# Wifi.net
KiCad netlist of a schematic drawn in Altium Designer
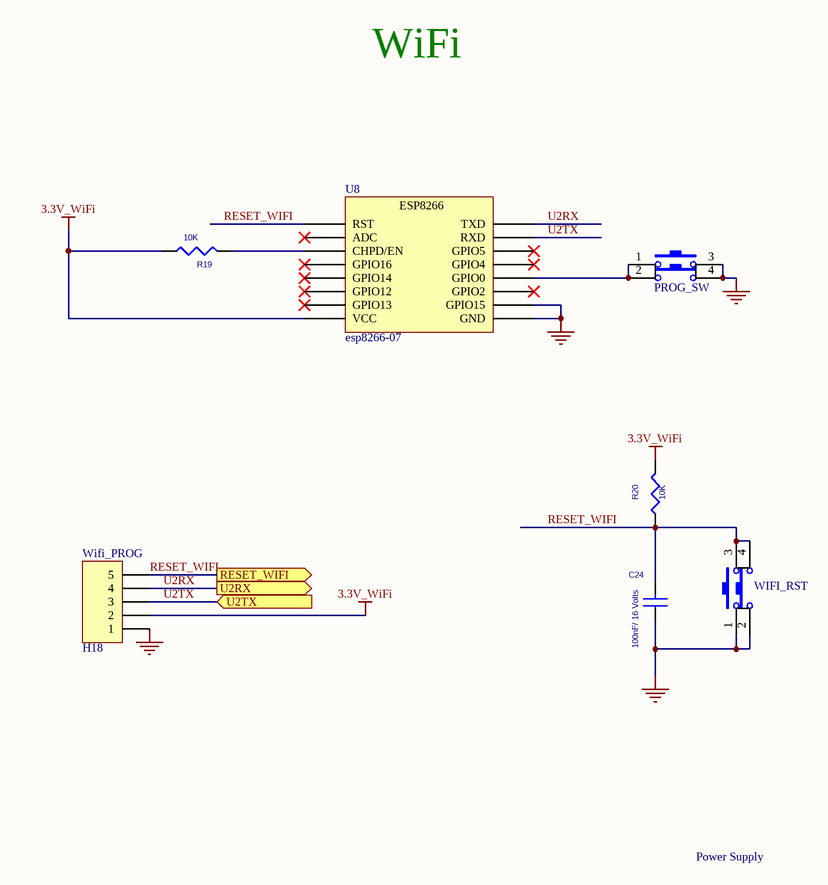
[diagram p0: Wifi.SchDoc]

(export (version "E")
  (design (tool "Eeschema 10.0.6"))
  (components
    (comp (ref "C24")
      (value "100nF/ 16 Volts")
      (footprint "CAP_CERAMIC")
      (libsource (lib "combined_cart_schematic_lib") (part "CAP NP"))
    )
    (comp (ref "PROG_SW")
      (value "SW-SMD")
      (footprint "SWITCH_SMD")
      (description "Switch")
      (fields (field (name "PUBLISHER") "Altium Limited"))
      (libsource (lib "combined_cart_schematic_lib") (part "SW-SMD"))
    )
    (comp (ref "R19")
      (value "10K")
      (footprint "RES_SMD")
      (libsource (lib "combined_cart_schematic_lib") (part "RESISTOR"))
    )
    (comp (ref "R20")
      (value "10K")
      (footprint "RES_SMD")
      (libsource (lib "combined_cart_schematic_lib") (part "RESISTOR"))
    )
    (comp (ref "U8")
      (value "esp8266-07")
      (footprint "esp8266-07")
      (fields (field (name "PUBLISHER") "Altium Limited"))
      (libsource (lib "combined_cart_schematic_lib") (part "esp8266-07"))
    )
    (comp (ref "Wifi_PROG")
      (value "H18")
      (footprint "1x5_single")
      (description "Header, 5-Pin")
      (fields (field (name "PUBLISHER") "Altium Limited"))
      (libsource (lib "combined_cart_schematic_lib") (part "Header 5"))
    )
    (comp (ref "WIFI_RST")
      (value "SW-SMD")
      (footprint "SWITCH_SMD")
      (description "Switch")
      (fields (field (name "PUBLISHER") "Altium Limited"))
      (libsource (lib "combined_cart_schematic_lib") (part "SW-SMD"))
    )
  )
  (nets
    (net (code "1") (name "/RESET_WIFI") (class "Default")
      (node (ref "C24") (pin "2") (pinfunction "2_2") (pintype "passive"))
      (node (ref "R20") (pin "1") (pinfunction "1_1") (pintype "passive"))
      (node (ref "U8") (pin "0") (pinfunction "RST_0") (pintype "passive"))
      (node (ref "WIFI_RST") (pin "3") (pintype "passive"))
      (node (ref "WIFI_RST") (pin "4") (pintype "passive"))
      (node (ref "Wifi_PROG") (pin "5") (pinfunction "5_5") (pintype "passive"))
    )
    (net (code "2") (name "/U2RX") (class "Default")
      (node (ref "U8") (pin "15") (pinfunction "TXD_15") (pintype "passive"))
      (node (ref "Wifi_PROG") (pin "4") (pinfunction "4_4") (pintype "passive"))
    )
    (net (code "3") (name "/U2TX") (class "Default")
      (node (ref "U8") (pin "14") (pinfunction "RXD_14") (pintype "passive"))
      (node (ref "Wifi_PROG") (pin "3") (pinfunction "3_3") (pintype "passive"))
    )
    (net (code "4") (name "3.3V_WiFi") (class "Default")
      (node (ref "R19") (pin "1") (pinfunction "1_1") (pintype "passive"))
      (node (ref "R20") (pin "2") (pinfunction "2_2") (pintype "passive"))
      (node (ref "U8") (pin "7") (pinfunction "VCC_7") (pintype "passive"))
      (node (ref "Wifi_PROG") (pin "2") (pinfunction "2_2") (pintype "passive"))
    )
    (net (code "5") (name "GND_POWER") (class "Default")
      (node (ref "C24") (pin "1") (pinfunction "1_1") (pintype "passive"))
      (node (ref "PROG_SW") (pin "3") (pintype "passive"))
      (node (ref "PROG_SW") (pin "4") (pintype "passive"))
      (node (ref "U8") (pin "8") (pinfunction "GND_8") (pintype "passive"))
      (node (ref "U8") (pin "9") (pinfunction "GPIO15_9") (pintype "passive"))
      (node (ref "WIFI_RST") (pin "1") (pintype "passive"))
      (node (ref "WIFI_RST") (pin "2") (pintype "passive"))
      (node (ref "Wifi_PROG") (pin "1") (pinfunction "1_1") (pintype "passive"))
    )
    (net (code "6") (name "Net-(U8-CHPD{slash}EN)") (class "Default")
      (node (ref "R19") (pin "2") (pinfunction "2_2") (pintype "passive"))
      (node (ref "U8") (pin "2") (pinfunction "CHPD/EN_2") (pintype "passive"))
    )
    (net (code "7") (name "Net-(U8-GPIO0)") (class "Default")
      (node (ref "PROG_SW") (pin "1") (pintype "passive"))
      (node (ref "PROG_SW") (pin "2") (pintype "passive"))
      (node (ref "U8") (pin "11") (pinfunction "GPIO0_11") (pintype "passive"))
    )
    (net (code "8") (name "unconnected-(U8-ADC-Pad1)") (class "Default")
      (node (ref "U8") (pin "1") (pinfunction "ADC_1") (pintype "passive+no_connect"))
    )
    (net (code "9") (name "unconnected-(U8-GPIO2-Pad10)") (class "Default")
      (node (ref "U8") (pin "10") (pinfunction "GPIO2_10") (pintype "passive+no_connect"))
    )
    (net (code "10") (name "unconnected-(U8-GPIO4-Pad12)") (class "Default")
      (node (ref "U8") (pin "12") (pinfunction "GPIO4_12") (pintype "passive+no_connect"))
    )
    (net (code "11") (name "unconnected-(U8-GPIO5-Pad13)") (class "Default")
      (node (ref "U8") (pin "13") (pinfunction "GPIO5_13") (pintype "passive+no_connect"))
    )
    (net (code "12") (name "unconnected-(U8-GPIO12-Pad5)") (class "Default")
      (node (ref "U8") (pin "5") (pinfunction "GPIO12_5") (pintype "passive+no_connect"))
    )
    (net (code "13") (name "unconnected-(U8-GPIO13-Pad6)") (class "Default")
      (node (ref "U8") (pin "6") (pinfunction "GPIO13_6") (pintype "passive+no_connect"))
    )
    (net (code "14") (name "unconnected-(U8-GPIO14-Pad4)") (class "Default")
      (node (ref "U8") (pin "4") (pinfunction "GPIO14_4") (pintype "passive+no_connect"))
    )
    (net (code "15") (name "unconnected-(U8-GPIO16-Pad3)") (class "Default")
      (node (ref "U8") (pin "3") (pinfunction "GPIO16_3") (pintype "passive+no_connect"))
    )
  )
)
